# Charging_1AOut1.net
KiCad netlist of a schematic drawn in Altium Designer
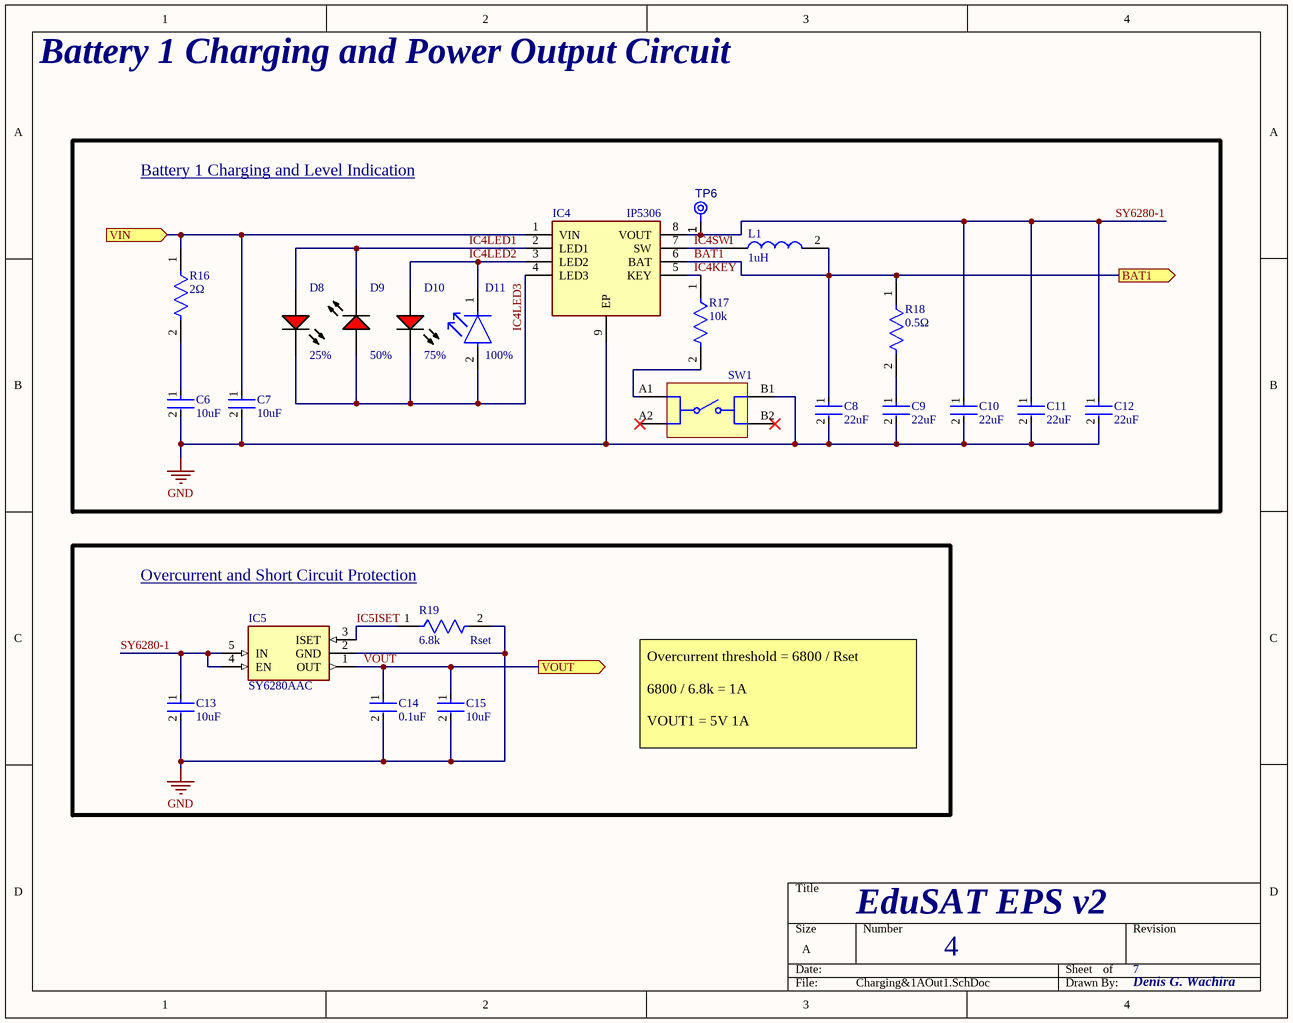
[diagram p0: Charging&1AOut1.SchDoc]

(export (version "E")
  (design (tool "Eeschema 10.0.6"))
  (components
    (comp (ref "C6")
      (value "10uF")
      (footprint "FP-CL21-IPC_A")
      (description "CL21 Series 0805 10uF 25V ±10% Tolerance X5R Multilayer Ceramic Chip Capacitor CL21A106KAYNNNE")
      (fields (field (name "TOLERANCE") "10%"))
      (libsource (lib "Altium Content Vault") (part "b4654b650e69147ec39a6b967a45e02"))
    )
    (comp (ref "C7")
      (value "10uF")
      (footprint "FP-CL21-IPC_A")
      (description "CL21 Series 0805 10uF 25V ±10% Tolerance X5R Multilayer Ceramic Chip Capacitor CL21A106KAYNNNE")
      (fields (field (name "TOLERANCE") "10%"))
      (libsource (lib "Altium Content Vault") (part "b4654b650e69147ec39a6b967a45e02"))
    )
    (comp (ref "C8")
      (value "22uF")
      (footprint "FP-CL21-IPC_C")
      (description "CL21 Series 0805 22uF 25V ±20% Tolerance X5R Multilayer Ceramic Chip Capacitor CL21A226MAYNNNE")
      (libsource (lib "Altium Content Vault") (part "b4654b650e69147ec39a6b967a45e02"))
    )
    (comp (ref "C9")
      (value "22uF")
      (footprint "FP-CL21-IPC_C")
      (description "CL21 Series 0805 22uF 25V ±20% Tolerance X5R Multilayer Ceramic Chip Capacitor CL21A226MAYNNNE")
      (libsource (lib "Altium Content Vault") (part "b4654b650e69147ec39a6b967a45e02"))
    )
    (comp (ref "C10")
      (value "22uF")
      (footprint "FP-CL21-IPC_C")
      (description "CL21 Series 0805 22uF 25V ±20% Tolerance X5R Multilayer Ceramic Chip Capacitor CL21A226MAYNNNE")
      (libsource (lib "Altium Content Vault") (part "b4654b650e69147ec39a6b967a45e02"))
    )
    (comp (ref "C11")
      (value "22uF")
      (footprint "FP-CL21-IPC_C")
      (description "CL21 Series 0805 22uF 25V ±20% Tolerance X5R Multilayer Ceramic Chip Capacitor CL21A226MAYNNNE")
      (libsource (lib "Altium Content Vault") (part "b4654b650e69147ec39a6b967a45e02"))
    )
    (comp (ref "C12")
      (value "22uF")
      (footprint "FP-CL21-IPC_C")
      (description "CL21 Series 0805 22uF 25V ±20% Tolerance X5R Multilayer Ceramic Chip Capacitor CL21A226MAYNNNE")
      (libsource (lib "Altium Content Vault") (part "b4654b650e69147ec39a6b967a45e02"))
    )
    (comp (ref "C13")
      (value "10uF")
      (footprint "FP-CL21-IPC_A")
      (description "CL21 Series 0805 10uF 25V ±10% Tolerance X5R Multilayer Ceramic Chip Capacitor CL21A106KAYNNNE")
      (fields (field (name "TOLERANCE") "10%"))
      (libsource (lib "Altium Content Vault") (part "b4654b650e69147ec39a6b967a45e02"))
    )
    (comp (ref "C14")
      (value "0.1uF")
      (footprint "FP-CL21-IPC_A")
      (description "50V 0.1uF X7R ±10% 0805 Multilayer Ceramic Capacitors MLCC - SMD/SMT ROHS TCC0805X7R104K500DT")
      (fields (field (name "TOLERANCE") "10%"))
      (libsource (lib "Altium Content Vault") (part "b4654b650e69147ec39a6b967a45e02"))
    )
    (comp (ref "C15")
      (value "10uF")
      (footprint "FP-CL21-IPC_A")
      (description "CL21 Series 0805 10uF 25V ±10% Tolerance X5R Multilayer Ceramic Chip Capacitor CL21A106KAYNNNE")
      (fields (field (name "TOLERANCE") "10%"))
      (libsource (lib "Altium Content Vault") (part "b4654b650e69147ec39a6b967a45e02"))
    )
    (comp (ref "D8")
      (value "25%")
      (footprint "LTST-C170KRKT_V")
      (description "LED Red,KT-0805R")
      (fields (field (name "MANUFACTURER") "Lite-On"))
      (libsource (lib "Altium Content Vault") (part "LED-RED-AK-2"))
    )
    (comp (ref "D9")
      (value "50%")
      (footprint "LTST-C170KRKT_V")
      (description "LED Red, KT-0805R")
      (fields (field (name "MANUFACTURER") "Lite-On"))
      (libsource (lib "Altium Content Vault") (part "LED-RED-AK-2"))
    )
    (comp (ref "D10")
      (value "75%")
      (footprint "LTST-C170KRKT_V")
      (description "LED Red, KT-0805R")
      (fields (field (name "MANUFACTURER") "Lite-On"))
      (libsource (lib "Altium Content Vault") (part "LED-RED-AK-2"))
    )
    (comp (ref "D11")
      (value "100%")
      (footprint "FP-LTST-C170GKT-MFG")
      (description "LED GREEN CLEAR SMD KT-0805G")
      (fields (field (name "VOLTAGE") "5V"))
      (libsource (lib "Altium Content Vault") (part "8706943c75ba83719d021d2fdc84c58"))
    )
    (comp (ref "IC4")
      (value "IP5306")
      (footprint "SamacSys:SOIC127P600X165-9N")
      (description "Integrated Circuit")
      (libsource (lib "IP5306") (part "IP5306"))
    )
    (comp (ref "IC5")
      (value "SY6280AAC")
      (footprint "SamacSys:SOT95P285X140-5N")
      (description "Integrated Circuit")
      (libsource (lib "*") (part "SY6280AAC"))
    )
    (comp (ref "L1")
      (value "1uH")
      (footprint "SamacSys:INDPM7366X300N")
      (description "Inductor MCS0630-1R0MN2")
      (fields (field (name "MANUFACTURER_PART_NUMBER") "MCS0630-1R0MN2"))
      (libsource (lib "*") (part "MCS0630-2R2MN2"))
    )
    (comp (ref "R16")
      (value "2Ω")
      (footprint "FP-CR0805-IPC_B")
      (description "Thick Film Chip Resistors 0805 2Ω 0.125W 1% 250ppm/°C \r\nRS-05L2R00FT")
      (fields (field (name "TOLERANCE") "1%"))
      (libsource (lib "Altium Content Vault") (part "1029c3af85768c4190bb7ad29bc67b5"))
    )
    (comp (ref "R17")
      (value "10k")
      (footprint "FP-MCR10-IPC_C")
      (description "Thick Film Chip Resistor, 0805, 10kΩ, 1%, 100ppm/°C, 0.125W, 150V \r\n0805W8F1002T5E")
      (fields (field (name "TOLERANCE") "1%"))
      (libsource (lib "Altium Content Vault") (part "1029c3af85768c4190bb7ad29bc67b5"))
    )
    (comp (ref "R18")
      (value "0.5Ω")
      (footprint "FP-MCR10-IPC_C")
      (description "Thick Film Chip Resistor, 0805, 0.5R, 1%, 100ppm/°C, 0.125W, 150V \r\n0805W8F500LT5E")
      (fields (field (name "TOLERANCE") "1%"))
      (libsource (lib "Altium Content Vault") (part "1029c3af85768c4190bb7ad29bc67b5"))
    )
    (comp (ref "R19")
      (value "6.8k          Rset")
      (footprint "FP-MCR10-IPC_C")
      (description "Thick Film Chip Resistor, 0805, 6.8kΩ, 1%, 100ppm/°C, 0.125W, 150V \r\n0805W8F6801T5E")
      (fields (field (name "TOLERANCE") "1%"))
      (libsource (lib "Altium Content Vault") (part "1029c3af85768c4190bb7ad29bc67b5"))
    )
    (comp (ref "SW1")
      (value "430181038816")
      (footprint "WS-TASV_L4.5W4.5H3.8_430181038816")
      (libsource (lib "Altium Content Vault") (part "SPST-NO_4P"))
    )
    (comp (ref "TP6")
      (value "TPAD6R")
      (footprint "TP06R")
      (description "0.6mm round")
      (libsource (lib "University of Nairobi") (part "CMP-001-0001-4"))
    )
  )
  (nets
    (net (code "1") (name "/BAT1") (class "Default")
      (node (ref "C8") (pin "1") (pinfunction "1_1") (pintype "passive"))
      (node (ref "IC4") (pin "6") (pinfunction "BAT_6") (pintype "passive"))
      (node (ref "L1") (pin "2") (pinfunction "2_2") (pintype "passive"))
      (node (ref "R18") (pin "1") (pinfunction "1_1") (pintype "passive"))
    )
    (net (code "2") (name "/IC4KEY") (class "Default")
      (node (ref "IC4") (pin "5") (pinfunction "KEY_5") (pintype "passive"))
      (node (ref "R17") (pin "1") (pinfunction "1_1") (pintype "passive"))
    )
    (net (code "3") (name "/IC4LED1") (class "Default")
      (node (ref "D8") (pin "1") (pinfunction "A_1") (pintype "passive"))
      (node (ref "D9") (pin "2") (pinfunction "K_2") (pintype "passive"))
      (node (ref "IC4") (pin "2") (pinfunction "LED1_2") (pintype "passive"))
    )
    (net (code "4") (name "/IC4LED2") (class "Default")
      (node (ref "D10") (pin "1") (pinfunction "A_1") (pintype "passive"))
      (node (ref "D11") (pin "1") (pinfunction "C_1") (pintype "passive"))
      (node (ref "IC4") (pin "3") (pinfunction "LED2_3") (pintype "passive"))
    )
    (net (code "5") (name "/IC4LED3") (class "Default")
      (node (ref "D10") (pin "2") (pinfunction "K_2") (pintype "passive"))
      (node (ref "D11") (pin "2") (pinfunction "A_2") (pintype "passive"))
      (node (ref "D8") (pin "2") (pinfunction "K_2") (pintype "passive"))
      (node (ref "D9") (pin "1") (pinfunction "A_1") (pintype "passive"))
      (node (ref "IC4") (pin "4") (pinfunction "LED3_4") (pintype "passive"))
    )
    (net (code "6") (name "/IC4SW") (class "Default")
      (node (ref "IC4") (pin "7") (pinfunction "SW_7") (pintype "passive"))
      (node (ref "L1") (pin "1") (pinfunction "1_1") (pintype "passive"))
    )
    (net (code "7") (name "/IC5ISET") (class "Default")
      (node (ref "IC5") (pin "3") (pinfunction "ISET_3") (pintype "input"))
      (node (ref "R19") (pin "1") (pinfunction "1_1") (pintype "passive"))
    )
    (net (code "8") (name "/SY6280-1") (class "Default")
      (node (ref "C10") (pin "1") (pinfunction "1_1") (pintype "passive"))
      (node (ref "C11") (pin "1") (pinfunction "1_1") (pintype "passive"))
      (node (ref "C12") (pin "1") (pinfunction "1_1") (pintype "passive"))
      (node (ref "C13") (pin "1") (pinfunction "1_1") (pintype "passive"))
      (node (ref "IC4") (pin "8") (pinfunction "VOUT_8") (pintype "passive"))
      (node (ref "IC5") (pin "4") (pinfunction "EN_4") (pintype "input"))
      (node (ref "IC5") (pin "5") (pinfunction "IN_5") (pintype "input"))
      (node (ref "TP6") (pin "1") (pinfunction "TP_1") (pintype "passive"))
    )
    (net (code "9") (name "/VIN") (class "Default")
      (node (ref "C7") (pin "1") (pinfunction "1_1") (pintype "passive"))
      (node (ref "IC4") (pin "1") (pinfunction "VIN_1") (pintype "passive"))
      (node (ref "R16") (pin "1") (pinfunction "1_1") (pintype "passive"))
    )
    (net (code "10") (name "/VOUT") (class "Default")
      (node (ref "C14") (pin "1") (pinfunction "1_1") (pintype "passive"))
      (node (ref "C15") (pin "1") (pinfunction "1_1") (pintype "passive"))
      (node (ref "IC5") (pin "1") (pinfunction "OUT_1") (pintype "output"))
    )
    (net (code "11") (name "GND") (class "Default")
      (node (ref "C10") (pin "2") (pinfunction "2_2") (pintype "passive"))
      (node (ref "C11") (pin "2") (pinfunction "2_2") (pintype "passive"))
      (node (ref "C12") (pin "2") (pinfunction "2_2") (pintype "passive"))
      (node (ref "C13") (pin "2") (pinfunction "2_2") (pintype "passive"))
      (node (ref "C14") (pin "2") (pinfunction "2_2") (pintype "passive"))
      (node (ref "C15") (pin "2") (pinfunction "2_2") (pintype "passive"))
      (node (ref "C6") (pin "2") (pinfunction "2_2") (pintype "passive"))
      (node (ref "C7") (pin "2") (pinfunction "2_2") (pintype "passive"))
      (node (ref "C8") (pin "2") (pinfunction "2_2") (pintype "passive"))
      (node (ref "C9") (pin "2") (pinfunction "2_2") (pintype "passive"))
      (node (ref "IC4") (pin "9") (pinfunction "EP_9") (pintype "passive"))
      (node (ref "IC5") (pin "2") (pinfunction "GND_2") (pintype "power_in"))
      (node (ref "R19") (pin "2") (pinfunction "2_2") (pintype "passive"))
      (node (ref "SW1") (pin "B1") (pinfunction "B1_B1") (pintype "passive"))
    )
    (net (code "12") (name "Net-(C6-Pad1)") (class "Default")
      (node (ref "C6") (pin "1") (pinfunction "1_1") (pintype "passive"))
      (node (ref "R16") (pin "2") (pinfunction "2_2") (pintype "passive"))
    )
    (net (code "13") (name "Net-(C9-Pad1)") (class "Default")
      (node (ref "C9") (pin "1") (pinfunction "1_1") (pintype "passive"))
      (node (ref "R18") (pin "2") (pinfunction "2_2") (pintype "passive"))
    )
    (net (code "14") (name "Net-(R17-Pad2)") (class "Default")
      (node (ref "R17") (pin "2") (pinfunction "2_2") (pintype "passive"))
      (node (ref "SW1") (pin "A1") (pinfunction "A1_A1") (pintype "passive"))
    )
    (net (code "15") (name "unconnected-(SW1-PadA2)") (class "Default")
      (node (ref "SW1") (pin "A2") (pinfunction "A2_A2") (pintype "passive+no_connect"))
    )
    (net (code "16") (name "unconnected-(SW1-PadB2)") (class "Default")
      (node (ref "SW1") (pin "B2") (pinfunction "B2_B2") (pintype "passive+no_connect"))
    )
  )
)
